# POWER.net
KiCad netlist of a schematic drawn in Altium Designer
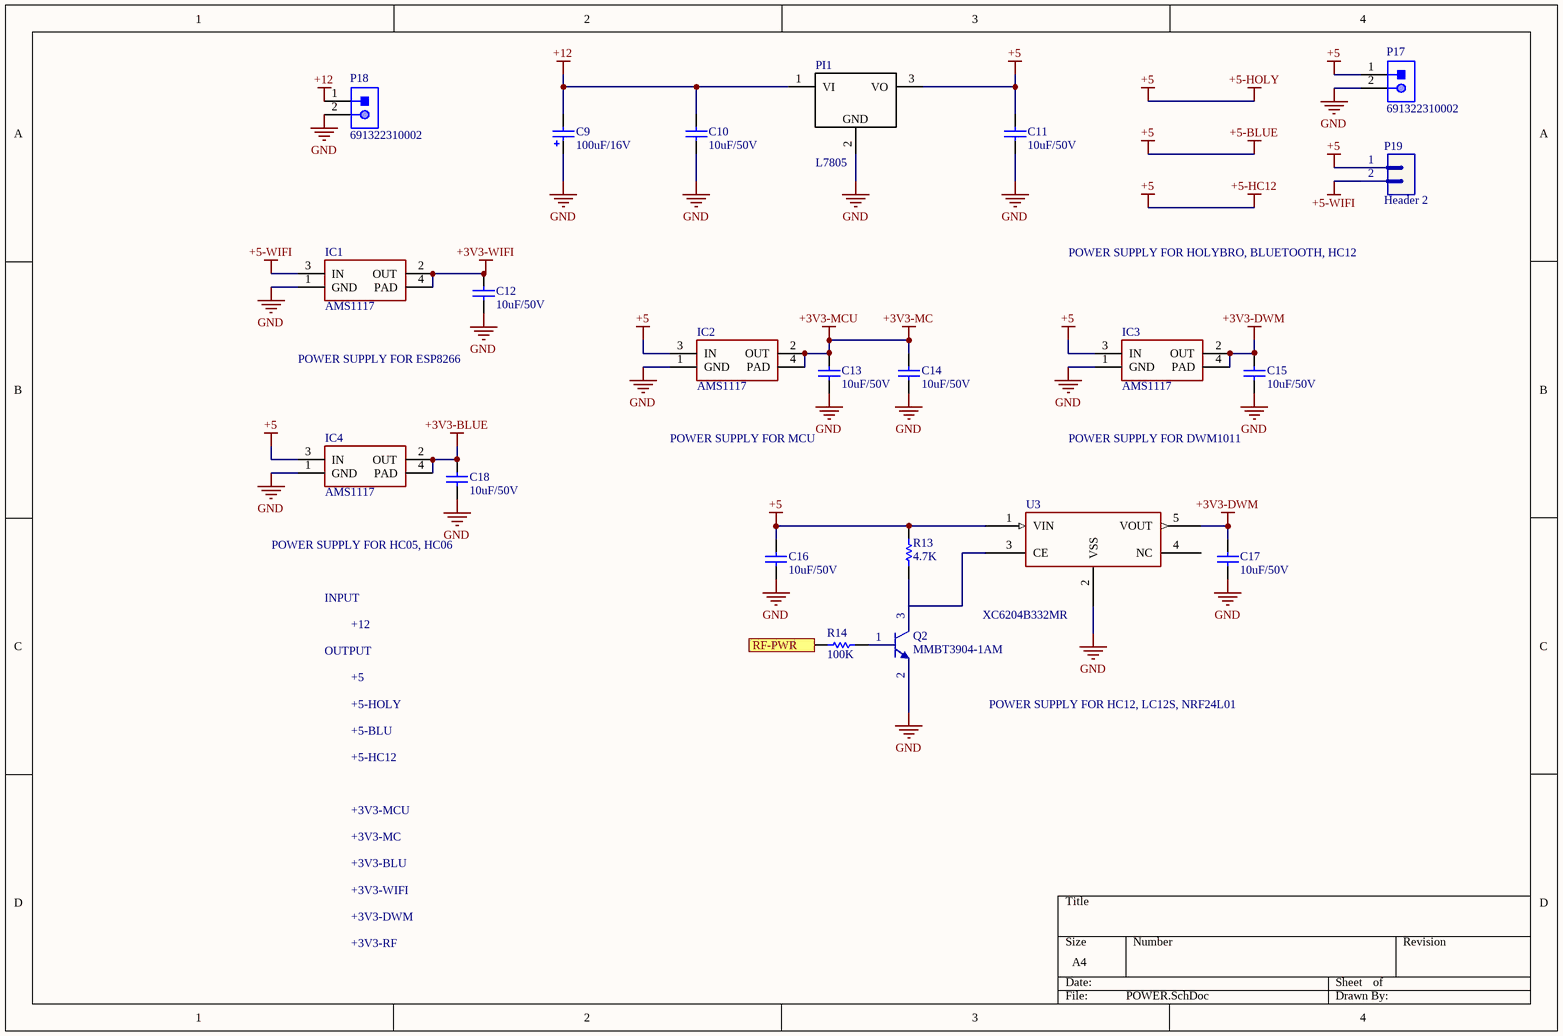
[diagram p0: POWER.SchDoc]

(export (version "E")
  (design (tool "Eeschema 10.0.6"))
  (components
    (comp (ref "C9")
      (value "100uF/16V")
      (footprint "CAP-SM-AL-SIZE-D-D6L6")
      (description "CAP ALUM 100UF 20% 16V SMD")
      (fields
        (field (name "MANUFACTURER") "Nichicon")
        (field (name "MANUFACTURER PART NUMBER") "UWX1C101MCL1GB")
      )
      (libsource (lib "Capacitor") (part "Cap-Al-100uF-16V-D6L5"))
    )
    (comp (ref "C10")
      (value "10uF/50V")
      (footprint "CAP-SM-0805")
      (description "CAP CER 10UF 50V X5R 0805")
      (fields
        (field (name "MANUFACTURER") "Yageo")
        (field (name "MANUFACTURER PART NUMBER") "CC0805KKX5R9BB106")
      )
      (libsource (lib "Capacitor") (part "Cap-10uF-50V-0805"))
    )
    (comp (ref "C11")
      (value "10uF/50V")
      (footprint "CAP-SM-0805")
      (description "CAP CER 10UF 50V X5R 0805")
      (fields
        (field (name "MANUFACTURER") "Yageo")
        (field (name "MANUFACTURER PART NUMBER") "CC0805KKX5R9BB106")
      )
      (libsource (lib "Capacitor") (part "Cap-10uF-50V-0805"))
    )
    (comp (ref "C12")
      (value "10uF/50V")
      (footprint "CAP-SM-0805")
      (description "CAP CER 10UF 50V X5R 0805")
      (fields
        (field (name "MANUFACTURER") "Yageo")
        (field (name "MANUFACTURER PART NUMBER") "CC0805KKX5R9BB106")
      )
      (libsource (lib "Capacitor") (part "Cap-10uF-50V-0805"))
    )
    (comp (ref "C13")
      (value "10uF/50V")
      (footprint "CAP-SM-0805")
      (description "CAP CER 10UF 50V X5R 0805")
      (fields
        (field (name "MANUFACTURER") "Yageo")
        (field (name "MANUFACTURER PART NUMBER") "CC0805KKX5R9BB106")
      )
      (libsource (lib "Capacitor") (part "Cap-10uF-50V-0805"))
    )
    (comp (ref "C14")
      (value "10uF/50V")
      (footprint "CAP-SM-0805")
      (description "CAP CER 10UF 50V X5R 0805")
      (fields
        (field (name "MANUFACTURER") "Yageo")
        (field (name "MANUFACTURER PART NUMBER") "CC0805KKX5R9BB106")
      )
      (libsource (lib "Capacitor") (part "Cap-10uF-50V-0805"))
    )
    (comp (ref "C15")
      (value "10uF/50V")
      (footprint "CAP-SM-0805")
      (description "CAP CER 10UF 50V X5R 0805")
      (fields
        (field (name "MANUFACTURER") "Yageo")
        (field (name "MANUFACTURER PART NUMBER") "CC0805KKX5R9BB106")
      )
      (libsource (lib "Capacitor") (part "Cap-10uF-50V-0805"))
    )
    (comp (ref "C16")
      (value "10uF/50V")
      (footprint "CAP-SM-0805")
      (description "CAP CER 10UF 50V X5R 0805")
      (fields
        (field (name "MANUFACTURER") "Yageo")
        (field (name "MANUFACTURER PART NUMBER") "CC0805KKX5R9BB106")
      )
      (libsource (lib "Capacitor") (part "Cap-10uF-50V-0805"))
    )
    (comp (ref "C17")
      (value "10uF/50V")
      (footprint "CAP-SM-0805")
      (description "CAP CER 10UF 50V X5R 0805")
      (fields
        (field (name "MANUFACTURER") "Yageo")
        (field (name "MANUFACTURER PART NUMBER") "CC0805KKX5R9BB106")
      )
      (libsource (lib "Capacitor") (part "Cap-10uF-50V-0805"))
    )
    (comp (ref "C18")
      (value "10uF/50V")
      (footprint "CAP-SM-0805")
      (description "CAP CER 10UF 50V X5R 0805")
      (fields
        (field (name "MANUFACTURER") "Yageo")
        (field (name "MANUFACTURER PART NUMBER") "CC0805KKX5R9BB106")
      )
      (libsource (lib "Capacitor") (part "Cap-10uF-50V-0805"))
    )
    (comp (ref "IC1")
      (value "AMS1117")
      (footprint "SOT223")
      (description "Available in 1.8V, 2.5V, 2.85V, 3.3V, 5V, and  Adjustable Versions")
      (libsource (lib "PI") (part "AMS1117"))
    )
    (comp (ref "IC2")
      (value "AMS1117")
      (footprint "SOT223")
      (description "Available in 1.8V, 2.5V, 2.85V, 3.3V, 5V, and  Adjustable Versions")
      (libsource (lib "PI") (part "AMS1117"))
    )
    (comp (ref "IC3")
      (value "AMS1117")
      (footprint "SOT223")
      (description "Available in 1.8V, 2.5V, 2.85V, 3.3V, 5V, and  Adjustable Versions")
      (libsource (lib "PI") (part "AMS1117"))
    )
    (comp (ref "IC4")
      (value "AMS1117")
      (footprint "SOT223")
      (description "Available in 1.8V, 2.5V, 2.85V, 3.3V, 5V, and  Adjustable Versions")
      (libsource (lib "PI") (part "AMS1117"))
    )
    (comp (ref "P17")
      (value "691322310002")
      (footprint "691322310002")
      (description "WR-TBL Serie 322 Horizontal PCB Header, Pluggable, pitch 3.81mm, 2p")
      (fields (field (name "PUBLISHER") "Wurth Elektronik"))
      (libsource (lib "o162719v243 Altium_WR-TBL (rev19a)") (part "691322310002"))
    )
    (comp (ref "P18")
      (value "691322310002")
      (footprint "691322310002")
      (description "WR-TBL Serie 322 Horizontal PCB Header, Pluggable, pitch 3.81mm, 2p")
      (fields (field (name "PUBLISHER") "Wurth Elektronik"))
      (libsource (lib "o162719v243 Altium_WR-TBL (rev19a)") (part "691322310002"))
    )
    (comp (ref "P19")
      (value "Header 2")
      (footprint "JP2")
      (description "Header, 2-Pin")
      (fields (field (name "PUBLISHER") "Altium Limited"))
      (libsource (lib "Header-connector") (part "Header 2"))
    )
    (comp (ref "PI1")
      (value "L7805")
      (footprint "D2PAK")
      (description "LINEAR REGULATOR 5.0V")
      (libsource (lib "vh_altium_library") (part "L7805-D2PAK"))
    )
    (comp (ref "Q2")
      (value "MMBT3904-1AM")
      (footprint "SOT23_NEX")
      (libsource (lib "BJT") (part "MMBT3904-1AM"))
    )
    (comp (ref "R13")
      (value "4.7K")
      (footprint "Resistor:RES-SM-0805")
      (description "RES SMD 4.7K OHM 5% 1/8W 0805")
      (fields
        (field (name "MANUFACTURER") "Yageo")
        (field (name "MANUFACTURER PART NUMBER") "RC0805JR-074K7L")
      )
      (libsource (lib "Resistor") (part "Res-4.7K-0805"))
    )
    (comp (ref "R14")
      (value "100K")
      (footprint "Resistor:RES-SM-0805")
      (description "RES 0 OHM JUMPER 0805")
      (fields
        (field (name "MANUFACTURER") "Vishay Dale")
        (field (name "MANUFACTURER PART NUMBER") "WSL080500000ZEA9")
      )
      (libsource (lib "Resistor") (part "Res-100K-0805"))
    )
    (comp (ref "U3")
      (value "XC6204B332MR")
      (footprint "XC6204/05_SOT-00")
      (fields (field (name "COPYRIGHT") "Copyright (C) 2018 Accelerated Designs. All rights reserved"))
      (libsource (lib "PI") (part "XC6204B332MR"))
    )
  )
  (nets
    (net (code "1") (name "+3V3-BLUE") (class "Default")
      (node (ref "C18") (pin "2") (pinfunction "2_2") (pintype "passive"))
      (node (ref "IC4") (pin "2") (pinfunction "OUT_2") (pintype "passive"))
      (node (ref "IC4") (pin "4") (pinfunction "PAD_4") (pintype "passive"))
    )
    (net (code "2") (name "+3V3-DWM") (class "Default")
      (node (ref "C15") (pin "2") (pinfunction "2_2") (pintype "passive"))
      (node (ref "C17") (pin "2") (pinfunction "2_2") (pintype "passive"))
      (node (ref "IC3") (pin "2") (pinfunction "OUT_2") (pintype "passive"))
      (node (ref "IC3") (pin "4") (pinfunction "PAD_4") (pintype "passive"))
      (node (ref "U3") (pin "5") (pinfunction "VOUT_5") (pintype "output"))
    )
    (net (code "3") (name "+3V3-MC") (class "Default")
      (node (ref "C13") (pin "2") (pinfunction "2_2") (pintype "passive"))
      (node (ref "C14") (pin "2") (pinfunction "2_2") (pintype "passive"))
      (node (ref "IC2") (pin "2") (pinfunction "OUT_2") (pintype "passive"))
      (node (ref "IC2") (pin "4") (pinfunction "PAD_4") (pintype "passive"))
    )
    (net (code "4") (name "+3V3-WIFI") (class "Default")
      (node (ref "C12") (pin "2") (pinfunction "2_2") (pintype "passive"))
      (node (ref "IC1") (pin "2") (pinfunction "OUT_2") (pintype "passive"))
      (node (ref "IC1") (pin "4") (pinfunction "PAD_4") (pintype "passive"))
    )
    (net (code "5") (name "+5") (class "Default")
      (node (ref "C11") (pin "2") (pinfunction "2_2") (pintype "passive"))
      (node (ref "C16") (pin "2") (pinfunction "2_2") (pintype "passive"))
      (node (ref "IC2") (pin "3") (pinfunction "IN_3") (pintype "passive"))
      (node (ref "IC3") (pin "3") (pinfunction "IN_3") (pintype "passive"))
      (node (ref "IC4") (pin "3") (pinfunction "IN_3") (pintype "passive"))
      (node (ref "P17") (pin "1") (pinfunction "1_1") (pintype "passive"))
      (node (ref "P19") (pin "1") (pinfunction "1_1") (pintype "passive"))
      (node (ref "PI1") (pin "3") (pinfunction "VO_3") (pintype "passive"))
      (node (ref "R13") (pin "2") (pinfunction "2_2") (pintype "passive"))
      (node (ref "U3") (pin "1") (pinfunction "VIN_1") (pintype "input"))
    )
    (net (code "6") (name "+5-WIFI") (class "Default")
      (node (ref "IC1") (pin "3") (pinfunction "IN_3") (pintype "passive"))
      (node (ref "P19") (pin "2") (pinfunction "2_2") (pintype "passive"))
    )
    (net (code "7") (name "+12") (class "Default")
      (node (ref "C10") (pin "2") (pinfunction "2_2") (pintype "passive"))
      (node (ref "C9") (pin "2") (pinfunction "2_2") (pintype "passive"))
      (node (ref "P18") (pin "1") (pinfunction "1_1") (pintype "passive"))
      (node (ref "PI1") (pin "1") (pinfunction "VI_1") (pintype "passive"))
    )
    (net (code "8") (name "/RF-PWR") (class "Default")
      (node (ref "R14") (pin "1") (pinfunction "1_1") (pintype "passive"))
    )
    (net (code "9") (name "GND") (class "Default")
      (node (ref "C10") (pin "1") (pinfunction "1_1") (pintype "passive"))
      (node (ref "C11") (pin "1") (pinfunction "1_1") (pintype "passive"))
      (node (ref "C12") (pin "1") (pinfunction "1_1") (pintype "passive"))
      (node (ref "C13") (pin "1") (pinfunction "1_1") (pintype "passive"))
      (node (ref "C14") (pin "1") (pinfunction "1_1") (pintype "passive"))
      (node (ref "C15") (pin "1") (pinfunction "1_1") (pintype "passive"))
      (node (ref "C16") (pin "1") (pinfunction "1_1") (pintype "passive"))
      (node (ref "C17") (pin "1") (pinfunction "1_1") (pintype "passive"))
      (node (ref "C18") (pin "1") (pinfunction "1_1") (pintype "passive"))
      (node (ref "C9") (pin "1") (pinfunction "1_1") (pintype "passive"))
      (node (ref "IC1") (pin "1") (pinfunction "GND_1") (pintype "passive"))
      (node (ref "IC2") (pin "1") (pinfunction "GND_1") (pintype "passive"))
      (node (ref "IC3") (pin "1") (pinfunction "GND_1") (pintype "passive"))
      (node (ref "IC4") (pin "1") (pinfunction "GND_1") (pintype "passive"))
      (node (ref "P17") (pin "2") (pinfunction "2_2") (pintype "passive"))
      (node (ref "P18") (pin "2") (pinfunction "2_2") (pintype "passive"))
      (node (ref "PI1") (pin "2") (pintype "passive"))
      (node (ref "Q2") (pin "2") (pinfunction "E_2") (pintype "passive"))
      (node (ref "U3") (pin "2") (pinfunction "VSS_2") (pintype "passive"))
    )
    (net (code "10") (name "Net-(Q2-B)") (class "Default")
      (node (ref "Q2") (pin "1") (pinfunction "B_1") (pintype "passive"))
      (node (ref "R14") (pin "2") (pinfunction "2_2") (pintype "passive"))
    )
    (net (code "11") (name "Net-(Q2-C)") (class "Default")
      (node (ref "Q2") (pin "3") (pinfunction "C_3") (pintype "passive"))
      (node (ref "R13") (pin "1") (pinfunction "1_1") (pintype "passive"))
    )
    (net (code "12") (name "unconnected-(U3-CE-Pad3)") (class "Default")
      (node (ref "U3") (pin "3") (pinfunction "CE_3") (pintype "passive"))
    )
    (net (code "13") (name "unconnected-(U3-NC-Pad4)") (class "Default")
      (node (ref "U3") (pin "4") (pinfunction "NC_4") (pintype "passive"))
    )
  )
)
